# 14_-_RTC_EEPROM_GPIO_TOUCH_SCREEN.net
KiCad netlist of a schematic drawn in Altium Designer
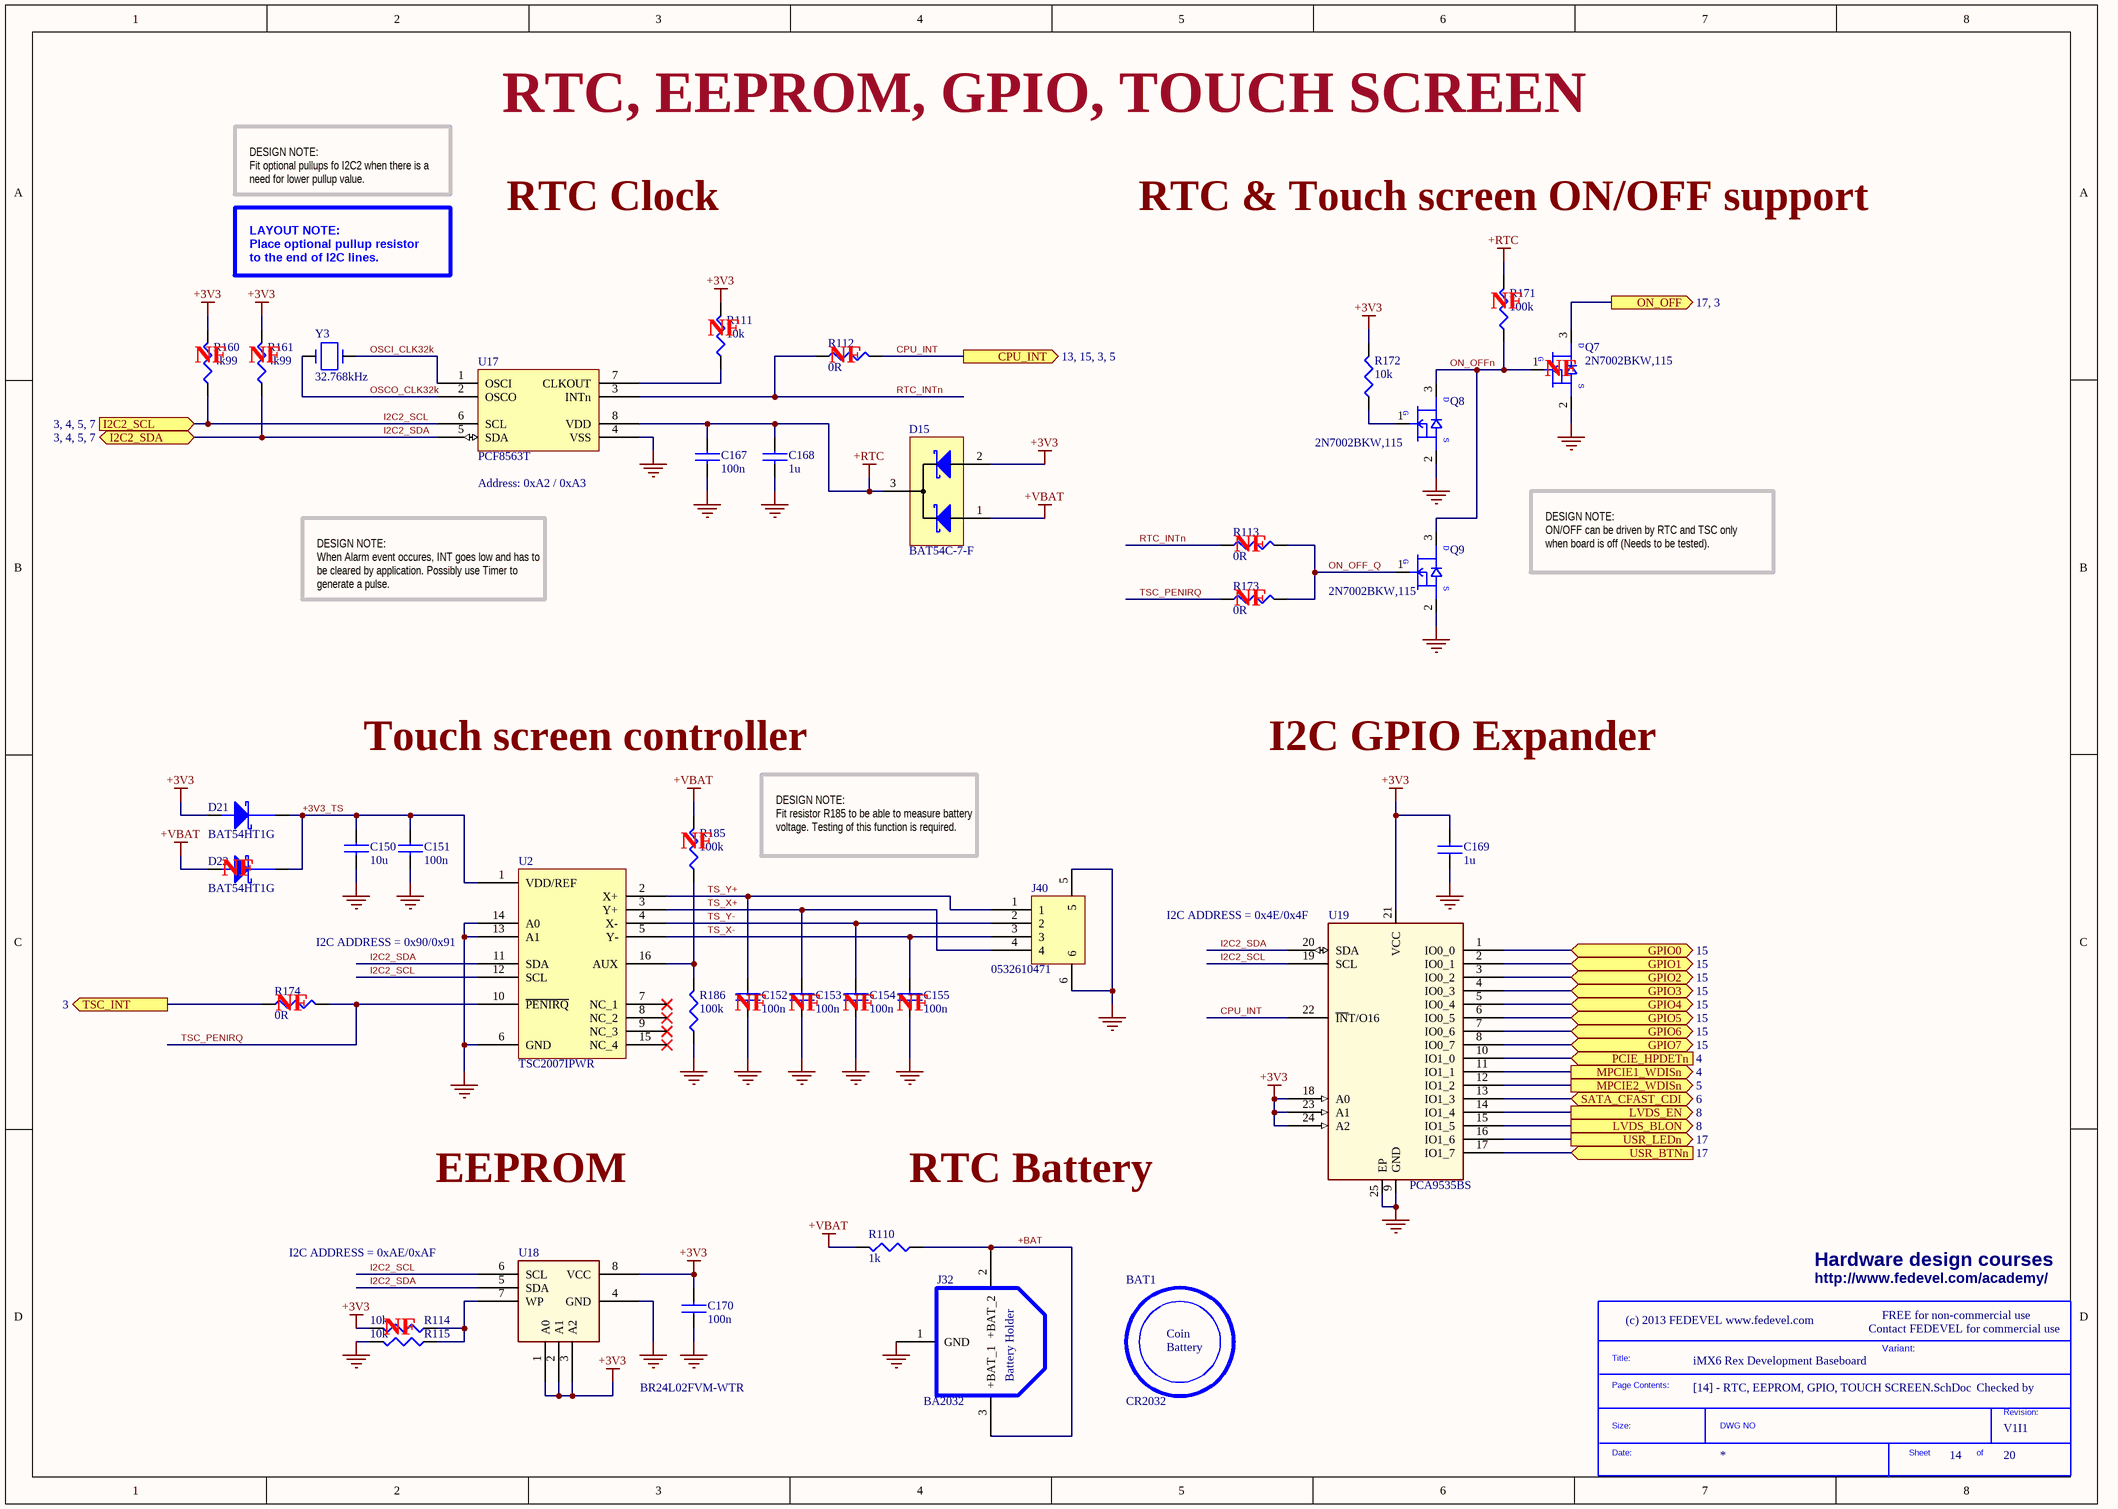
[diagram p0: [14] - RTC, EEPROM, GPIO, TOUCH SCREEN.SchDoc]

(export (version "E")
  (design (tool "Eeschema 10.0.6"))
  (components
    (comp (ref "BAT1")
      (value "CR2032")
      (description "BATTERY LITHIUM COIN 3V 20MM")
      (fields
        (field (name "MANUFACTURER") "Panasonic - BSG")
        (field (name ".CHECKED SCH") "RF")
        (field (name ".CHECKED PCB") "RF")
      )
      (libsource (lib "Integrated_Library_RF_FEB_2012") (part "CR2032"))
    )
    (comp (ref "C150")
      (value "10u")
      (footprint "C0603")
      (description "CAP CER 10UF 6.3V X5R 20% 0603")
      (fields
        (field (name "MANUFACTURER") "TDK Corporation")
        (field (name "MANUFACTURER PART NUMBER") "C1608X5R0J106M")
      )
      (libsource (lib "Integrated_Library_RF_FEB_2012") (part "C1608X5R0J106M"))
    )
    (comp (ref "C151")
      (value "100n")
      (footprint "C0402")
      (description "CAP CER .10UF 50V X5R 10% 0402")
      (fields
        (field (name "MANUFACTURER") "TDK Corporation")
        (field (name "MANUFACTURER PART NUMBER") "C1005X5R1H104K")
      )
      (libsource (lib "Integrated_Library_RF_FEB_2012") (part "C1005X5R1H104K"))
    )
    (comp (ref "C152")
      (value "100n")
      (footprint "C0402")
      (description "CAP CER .10UF 50V X5R 10% 0402")
      (fields
        (field (name "MANUFACTURER") "TDK Corporation")
        (field (name "MANUFACTURER PART NUMBER") "C1005X5R1H104K")
      )
      (libsource (lib "Integrated_Library_RF_FEB_2012") (part "C1005X5R1H104K"))
    )
    (comp (ref "C153")
      (value "100n")
      (footprint "C0402")
      (description "CAP CER .10UF 50V X5R 10% 0402")
      (fields
        (field (name "MANUFACTURER") "TDK Corporation")
        (field (name "MANUFACTURER PART NUMBER") "C1005X5R1H104K")
      )
      (libsource (lib "Integrated_Library_RF_FEB_2012") (part "C1005X5R1H104K"))
    )
    (comp (ref "C154")
      (value "100n")
      (footprint "C0402")
      (description "CAP CER .10UF 50V X5R 10% 0402")
      (fields
        (field (name "MANUFACTURER") "TDK Corporation")
        (field (name "MANUFACTURER PART NUMBER") "C1005X5R1H104K")
      )
      (libsource (lib "Integrated_Library_RF_FEB_2012") (part "C1005X5R1H104K"))
    )
    (comp (ref "C155")
      (value "100n")
      (footprint "C0402")
      (description "CAP CER .10UF 50V X5R 10% 0402")
      (fields
        (field (name "MANUFACTURER") "TDK Corporation")
        (field (name "MANUFACTURER PART NUMBER") "C1005X5R1H104K")
      )
      (libsource (lib "Integrated_Library_RF_FEB_2012") (part "C1005X5R1H104K"))
    )
    (comp (ref "C167")
      (value "100n")
      (footprint "C0402")
      (description "CAP CER .10UF 50V X5R 10% 0402")
      (fields
        (field (name "MANUFACTURER") "TDK Corporation")
        (field (name "MANUFACTURER PART NUMBER") "C1005X5R1H104K")
      )
      (libsource (lib "Integrated_Library_RF_FEB_2012") (part "C1005X5R1H104K"))
    )
    (comp (ref "C168")
      (value "1u")
      (footprint "C0402")
      (description "CAP CER 1.0UF 16V X5R 0402")
      (fields
        (field (name "MANUFACTURER") "TDK Corporation")
        (field (name "MANUFACTURER PART NUMBER") "C1005X5R1C105K")
      )
      (libsource (lib "Integrated_Library_RF_FEB_2012") (part "C1005X5R1C105K"))
    )
    (comp (ref "C169")
      (value "1u")
      (footprint "C0402")
      (description "CAP CER 1.0UF 16V X5R 0402")
      (fields
        (field (name "MANUFACTURER") "TDK Corporation")
        (field (name "MANUFACTURER PART NUMBER") "C1005X5R1C105K")
      )
      (libsource (lib "Integrated_Library_RF_FEB_2012") (part "C1005X5R1C105K"))
    )
    (comp (ref "C170")
      (value "100n")
      (footprint "C0402")
      (description "CAP CER .10UF 50V X5R 10% 0402")
      (fields
        (field (name "MANUFACTURER") "TDK Corporation")
        (field (name "MANUFACTURER PART NUMBER") "C1005X5R1H104K")
      )
      (libsource (lib "Integrated_Library_RF_FEB_2012") (part "C1005X5R1H104K"))
    )
    (comp (ref "D15")
      (value "BAT54C-7-F")
      (footprint "SOT-23-3-123")
      (description "DIODE SCHOTTKY DUAL 30V SOT23-3")
      (fields (field (name "MANUFACTURER") "Diodes Inc"))
      (libsource (lib "Integrated_Library_RF_FEB_2012") (part "BAT54C-7-F"))
    )
    (comp (ref "D21")
      (value "BAT54HT1G")
      (footprint "SOD323")
      (description "DIODE SCHOTTKY 30V 0.2A SOD323")
      (fields
        (field (name "MANUFACTURER") "Fairchild Semiconductor")
        (field (name ".CREATOR") "MM")
        (field (name ".CHECKED PCB") "RF, used by MM")
        (field (name ".CHECKED SCH") "MM")
      )
      (libsource (lib "Integrated_Library_RF_FEB_2012") (part "BAT54HT1G"))
    )
    (comp (ref "D22")
      (value "BAT54HT1G")
      (footprint "SOD323")
      (description "DIODE SCHOTTKY 30V 0.2A SOD323")
      (fields
        (field (name "MANUFACTURER") "Fairchild Semiconductor")
        (field (name ".CREATOR") "MM")
        (field (name ".CHECKED PCB") "RF, used by MM")
        (field (name ".CHECKED SCH") "MM")
      )
      (libsource (lib "Integrated_Library_RF_FEB_2012") (part "BAT54HT1G"))
    )
    (comp (ref "J32")
      (value "BA2032")
      (footprint "BA2032")
      (description "HOLDER COIN CELL CR2032 EJECT")
      (fields
        (field (name "MANUFACTURER") "MPD (Memory Protection Devices)")
        (field (name ".CREATOR") "MM")
        (field (name ".CHECKED PCB") "MM")
        (field (name ".CHECKED SCH") "RF, used by MM")
      )
      (libsource (lib "Integrated_Library_RF_FEB_2012") (part "BA2032"))
    )
    (comp (ref "J40")
      (value "0532610471")
      (footprint "0532610471")
      (description "CONN HEADER 4POS 1.25MM R/A SMD")
      (fields
        (field (name "MANUFACTURER") "Molex Inc")
        (field (name ".CREATOR") "MM")
        (field (name ".CHECKED PCB") "MM")
        (field (name ".CHECKED SCH") "MM")
      )
      (libsource (lib "Integrated_Library_RF_FEB_2012") (part "0532610471"))
    )
    (comp (ref "Q7")
      (value "2N7002BKW,115")
      (footprint "SC70_SOT323")
      (description "MOSFET N-CH 60V 310MA SOT323")
      (fields
        (field (name "MANUFACTURER") "NXP Semiconductors")
        (field (name ".CHECKED PCB") "RF")
        (field (name ".CHECKED SCH") "RF")
      )
      (libsource (lib "Integrated_Library_RF_FEB_2012") (part "2N7002BKW,115"))
    )
    (comp (ref "Q8")
      (value "2N7002BKW,115")
      (footprint "SC70_SOT323")
      (description "MOSFET N-CH 60V 310MA SOT323")
      (fields
        (field (name "MANUFACTURER") "NXP Semiconductors")
        (field (name ".CHECKED PCB") "RF")
        (field (name ".CHECKED SCH") "RF")
      )
      (libsource (lib "Integrated_Library_RF_FEB_2012") (part "2N7002BKW,115"))
    )
    (comp (ref "Q9")
      (value "2N7002BKW,115")
      (footprint "SC70_SOT323")
      (description "MOSFET N-CH 60V 310MA SOT323")
      (fields
        (field (name "MANUFACTURER") "NXP Semiconductors")
        (field (name ".CHECKED PCB") "RF")
        (field (name ".CHECKED SCH") "RF")
      )
      (libsource (lib "Integrated_Library_RF_FEB_2012") (part "2N7002BKW,115"))
    )
    (comp (ref "R110")
      (value "1k")
      (footprint "R0402")
      (description "RES 1.00K OHM 1/16W 1% 0402 SMD")
      (fields
        (field (name "MANUFACTURER") "Yageo")
        (field (name "MANUFACTURER PART NUMBER") "RC0402FR-071KL")
      )
      (libsource (lib "Integrated_Library_RF_FEB_2012") (part "RC0402FR-071KL"))
    )
    (comp (ref "R111")
      (value "10k")
      (footprint "R0402")
      (description "RES 10.0K OHM 1/16W 1% 0402 SMD")
      (fields
        (field (name "MANUFACTURER") "Yageo")
        (field (name "MANUFACTURER PART NUMBER") "RC0402FR-0710KL")
      )
      (libsource (lib "Integrated_Library_RF_FEB_2012") (part "RC0402FR-0710KL"))
    )
    (comp (ref "R112")
      (value "0R")
      (footprint "R0402")
      (description "RES 0.0 OHM 1/16W 0402 SMD")
      (fields
        (field (name "MANUFACTURER") "Yageo")
        (field (name "MANUFACTURER PART NUMBER") "RC0402JR-070RL")
      )
      (libsource (lib "Integrated_Library_RF_FEB_2012") (part "RC0402JR-070RL"))
    )
    (comp (ref "R113")
      (value "0R")
      (footprint "R0402")
      (description "RES 0.0 OHM 1/16W 0402 SMD")
      (fields
        (field (name "MANUFACTURER") "Yageo")
        (field (name "MANUFACTURER PART NUMBER") "RC0402JR-070RL")
      )
      (libsource (lib "Integrated_Library_RF_FEB_2012") (part "RC0402JR-070RL"))
    )
    (comp (ref "R114")
      (value "10k")
      (footprint "R0402")
      (description "RES 10.0K OHM 1/16W 1% 0402 SMD")
      (fields
        (field (name "MANUFACTURER") "Yageo")
        (field (name "MANUFACTURER PART NUMBER") "RC0402FR-0710KL")
      )
      (libsource (lib "Integrated_Library_RF_FEB_2012") (part "RC0402FR-0710KL"))
    )
    (comp (ref "R115")
      (value "10k")
      (footprint "R0402")
      (description "RES 10.0K OHM 1/16W 1% 0402 SMD")
      (fields
        (field (name "MANUFACTURER") "Yageo")
        (field (name "MANUFACTURER PART NUMBER") "RC0402FR-0710KL")
      )
      (libsource (lib "Integrated_Library_RF_FEB_2012") (part "RC0402FR-0710KL"))
    )
    (comp (ref "R160")
      (value "4k99")
      (footprint "R0402")
      (description "RES TF 4.99K OHM 1% 1/16W 0402")
      (fields
        (field (name "MANUFACTURER") "Stackpole Electronics Inc")
        (field (name "MANUFACTURER PART NUMBER") "RMCF0402FT4K99")
      )
      (libsource (lib "Integrated_Library_RF_FEB_2012") (part "RMCF0402FT4K99"))
    )
    (comp (ref "R161")
      (value "4k99")
      (footprint "R0402")
      (description "RES TF 4.99K OHM 1% 1/16W 0402")
      (fields
        (field (name "MANUFACTURER") "Stackpole Electronics Inc")
        (field (name "MANUFACTURER PART NUMBER") "RMCF0402FT4K99")
      )
      (libsource (lib "Integrated_Library_RF_FEB_2012") (part "RMCF0402FT4K99"))
    )
    (comp (ref "R171")
      (value "100k")
      (footprint "R0402")
      (description "RES 100K OHM 1/16W 1% 0402 SMD")
      (fields
        (field (name "MANUFACTURER") "Stackpole Electronics Inc")
        (field (name "MANUFACTURER PART NUMBER") "RMCF0402FT100K")
      )
      (libsource (lib "Integrated_Library_RF_FEB_2012") (part "RMCF0402FT100K"))
    )
    (comp (ref "R172")
      (value "10k")
      (footprint "R0402")
      (description "RES 10.0K OHM 1/16W 1% 0402 SMD")
      (fields
        (field (name "MANUFACTURER") "Yageo")
        (field (name "MANUFACTURER PART NUMBER") "RC0402FR-0710KL")
      )
      (libsource (lib "Integrated_Library_RF_FEB_2012") (part "RC0402FR-0710KL"))
    )
    (comp (ref "R173")
      (value "0R")
      (footprint "R0402")
      (description "RES 0.0 OHM 1/16W 0402 SMD")
      (fields
        (field (name "MANUFACTURER") "Yageo")
        (field (name "MANUFACTURER PART NUMBER") "RC0402JR-070RL")
      )
      (libsource (lib "Integrated_Library_RF_FEB_2012") (part "RC0402JR-070RL"))
    )
    (comp (ref "R174")
      (value "0R")
      (footprint "R0402")
      (description "RES 0.0 OHM 1/16W 0402 SMD")
      (fields
        (field (name "MANUFACTURER") "Yageo")
        (field (name "MANUFACTURER PART NUMBER") "RC0402JR-070RL")
      )
      (libsource (lib "Integrated_Library_RF_FEB_2012") (part "RC0402JR-070RL"))
    )
    (comp (ref "R185")
      (value "100k")
      (footprint "R0402")
      (description "RES 100K OHM 1/16W 1% 0402 SMD")
      (fields
        (field (name "MANUFACTURER") "Stackpole Electronics Inc")
        (field (name "MANUFACTURER PART NUMBER") "RMCF0402FT100K")
      )
      (libsource (lib "Integrated_Library_RF_FEB_2012") (part "RMCF0402FT100K"))
    )
    (comp (ref "R186")
      (value "100k")
      (footprint "R0402")
      (description "RES 100K OHM 1/16W 1% 0402 SMD")
      (fields
        (field (name "MANUFACTURER") "Stackpole Electronics Inc")
        (field (name "MANUFACTURER PART NUMBER") "RMCF0402FT100K")
      )
      (libsource (lib "Integrated_Library_RF_FEB_2012") (part "RMCF0402FT100K"))
    )
    (comp (ref "U2")
      (value "TSC2007IPWR")
      (footprint "PW (R-PDGO-G16)")
      (description "IC TOUCH SCREEN 12BIT 16TSSOP")
      (fields
        (field (name "MANUFACTURER") "Texas Instruments")
        (field (name ".CREATOR") "MM")
        (field (name ".CHECKED PCB") "MM")
        (field (name ".CHECKED SCH") "MM")
      )
      (libsource (lib "Integrated_Library_RF_FEB_2012") (part "TSC2007IPWR"))
    )
    (comp (ref "U17")
      (value "PCF8563T")
      (footprint "8_SOIC_3.9MM")
      (description "IC REAL TIME CLK/CALENDAR 8-SOIC")
      (fields
        (field (name "MANUFACTURER") "NXP Semiconductors")
        (field (name "MANUFACTURER PART NUMBER") "PCF8563T/F4,118")
      )
      (libsource (lib "Integrated_Library_RF_FEB_2012") (part "PCF8563T"))
    )
    (comp (ref "U18")
      (value "BR24L02FVM-WTR")
      (footprint "MSOP8 _SMALLER")
      (description "IC EEPROM 2KBIT 400KHZ 8MSOP")
      (fields
        (field (name "MANUFACTURER") "Rohm Semiconductor")
        (field (name ".CHECKED PCB") "RF")
        (field (name ".CHECKED SCH") "RF")
      )
      (libsource (lib "Integrated_Library_RF_FEB_2012") (part "BR24L02FVM-WTR"))
    )
    (comp (ref "U19")
      (value "PCA9535BS")
      (footprint "HVQFN24_4x4MM")
      (description "IC I/O EXPANDER I2C 16B 24HVQFN")
      (fields
        (field (name "MANUFACTURER") "NXP Semiconductors")
        (field (name "MANUFACTURER PART NUMBER") "PCA9535BS,118")
        (field (name ".CHECKED PCB") "RF")
        (field (name ".CHECKED SCH") "RF")
      )
      (libsource (lib "Integrated_Library_RF_FEB_2012") (part "PCA9535BS,118"))
    )
    (comp (ref "Y3")
      (value "32.768kHz")
      (footprint "ABS06")
      (description "CRYSTAL 32.768 KHZ 9.0 PF SMD")
      (fields
        (field (name "MANUFACTURER") "Abracon Corporation")
        (field (name "MANUFACTURER PART NUMBER") "ABS06-32.768KHZ-9-1-T")
      )
      (libsource (lib "Integrated_Library_RF_FEB_2012") (part "ABS06-32.768KHZ-9-1-T"))
    )
  )
  (nets
    (net (code "1") (name "+3V3") (class "Default")
      (node (ref "C169") (pin "2") (pinfunction "2_2") (pintype "passive"))
      (node (ref "C170") (pin "2") (pinfunction "2_2") (pintype "passive"))
      (node (ref "D15") (pin "2") (pinfunction "2_2") (pintype "passive"))
      (node (ref "D21") (pin "2") (pinfunction "Anode_2") (pintype "passive"))
      (node (ref "R111") (pin "2") (pinfunction "2_2") (pintype "passive"))
      (node (ref "R114") (pin "2") (pinfunction "2_2") (pintype "passive"))
      (node (ref "R160") (pin "2") (pinfunction "2_2") (pintype "passive"))
      (node (ref "R161") (pin "2") (pinfunction "2_2") (pintype "passive"))
      (node (ref "R172") (pin "2") (pinfunction "2_2") (pintype "passive"))
      (node (ref "U18") (pin "1") (pinfunction "A0_1") (pintype "passive"))
      (node (ref "U18") (pin "2") (pinfunction "A1_2") (pintype "passive"))
      (node (ref "U18") (pin "3") (pinfunction "A2_3") (pintype "passive"))
      (node (ref "U18") (pin "8") (pinfunction "VCC_8") (pintype "power_in"))
      (node (ref "U19") (pin "18") (pinfunction "A0_18") (pintype "input"))
      (node (ref "U19") (pin "21") (pinfunction "VCC_21") (pintype "power_in"))
      (node (ref "U19") (pin "23") (pinfunction "A1_23") (pintype "input"))
      (node (ref "U19") (pin "24") (pinfunction "A2_24") (pintype "input"))
    )
    (net (code "2") (name "+RTC") (class "Default")
      (node (ref "C167") (pin "1") (pinfunction "1_1") (pintype "passive"))
      (node (ref "C168") (pin "1") (pinfunction "1_1") (pintype "passive"))
      (node (ref "D15") (pin "3") (pinfunction "3_3") (pintype "passive"))
      (node (ref "R171") (pin "2") (pinfunction "2_2") (pintype "passive"))
      (node (ref "U17") (pin "8") (pinfunction "VDD_8") (pintype "power_in"))
    )
    (net (code "3") (name "+VBAT") (class "Default")
      (node (ref "D15") (pin "1") (pinfunction "1_1") (pintype "passive"))
      (node (ref "D22") (pin "2") (pinfunction "Anode_2") (pintype "passive"))
      (node (ref "R110") (pin "2") (pinfunction "2_2") (pintype "passive"))
      (node (ref "R185") (pin "2") (pinfunction "2_2") (pintype "passive"))
    )
    (net (code "4") (name "/+3V3_TS") (class "Default")
      (node (ref "C150") (pin "1") (pinfunction "1_1") (pintype "passive"))
      (node (ref "C151") (pin "1") (pinfunction "1_1") (pintype "passive"))
      (node (ref "D21") (pin "1") (pinfunction "Cathode_1") (pintype "passive"))
      (node (ref "D22") (pin "1") (pinfunction "Cathode_1") (pintype "passive"))
      (node (ref "U2") (pin "1") (pinfunction "VDD/REF_1") (pintype "passive"))
    )
    (net (code "5") (name "/+BAT") (class "Default")
      (node (ref "J32") (pin "2") (pinfunction "+BAT_2_2") (pintype "passive"))
      (node (ref "J32") (pin "3") (pinfunction "+BAT_1_3") (pintype "passive"))
      (node (ref "R110") (pin "1") (pinfunction "1_1") (pintype "passive"))
    )
    (net (code "6") (name "/CPU_INT") (class "Default")
      (node (ref "R112") (pin "2") (pinfunction "2_2") (pintype "passive"))
      (node (ref "U19") (pin "22") (pinfunction "~{IN}T/O16_22") (pintype "passive"))
    )
    (net (code "7") (name "/GPIO0") (class "Default")
      (node (ref "U19") (pin "1") (pinfunction "IO0_0_1") (pintype "passive"))
    )
    (net (code "8") (name "/GPIO1") (class "Default")
      (node (ref "U19") (pin "2") (pinfunction "IO0_1_2") (pintype "passive"))
    )
    (net (code "9") (name "/GPIO2") (class "Default")
      (node (ref "U19") (pin "3") (pinfunction "IO0_2_3") (pintype "passive"))
    )
    (net (code "10") (name "/GPIO3") (class "Default")
      (node (ref "U19") (pin "4") (pinfunction "IO0_3_4") (pintype "passive"))
    )
    (net (code "11") (name "/GPIO4") (class "Default")
      (node (ref "U19") (pin "5") (pinfunction "IO0_4_5") (pintype "passive"))
    )
    (net (code "12") (name "/GPIO5") (class "Default")
      (node (ref "U19") (pin "6") (pinfunction "IO0_5_6") (pintype "passive"))
    )
    (net (code "13") (name "/GPIO6") (class "Default")
      (node (ref "U19") (pin "7") (pinfunction "IO0_6_7") (pintype "passive"))
    )
    (net (code "14") (name "/GPIO7") (class "Default")
      (node (ref "U19") (pin "8") (pinfunction "IO0_7_8") (pintype "passive"))
    )
    (net (code "15") (name "/I2C2_SCL") (class "Default")
      (node (ref "R160") (pin "1") (pinfunction "1_1") (pintype "passive"))
      (node (ref "U17") (pin "6") (pinfunction "SCL_6") (pintype "passive"))
      (node (ref "U18") (pin "6") (pinfunction "SCL_6") (pintype "passive"))
      (node (ref "U19") (pin "19") (pinfunction "SCL_19") (pintype "passive"))
      (node (ref "U2") (pin "12") (pinfunction "SCL_12") (pintype "passive"))
    )
    (net (code "16") (name "/I2C2_SDA") (class "Default")
      (node (ref "R161") (pin "1") (pinfunction "1_1") (pintype "passive"))
      (node (ref "U17") (pin "5") (pinfunction "SDA_5") (pintype "bidirectional"))
      (node (ref "U18") (pin "5") (pinfunction "SDA_5") (pintype "passive"))
      (node (ref "U19") (pin "20") (pinfunction "SDA_20") (pintype "bidirectional"))
      (node (ref "U2") (pin "11") (pinfunction "SDA_11") (pintype "passive"))
    )
    (net (code "17") (name "/LVDS_BLON") (class "Default")
      (node (ref "U19") (pin "15") (pinfunction "IO1_5_15") (pintype "passive"))
    )
    (net (code "18") (name "/LVDS_EN") (class "Default")
      (node (ref "U19") (pin "14") (pinfunction "IO1_4_14") (pintype "passive"))
    )
    (net (code "19") (name "/MPCIE1_WDISn") (class "Default")
      (node (ref "U19") (pin "11") (pinfunction "IO1_1_11") (pintype "passive"))
    )
    (net (code "20") (name "/MPCIE2_WDISn") (class "Default")
      (node (ref "U19") (pin "12") (pinfunction "IO1_2_12") (pintype "passive"))
    )
    (net (code "21") (name "/ON_OFF") (class "Default")
      (node (ref "Q7") (pin "3") (pinfunction "DRAIN_3") (pintype "passive"))
    )
    (net (code "22") (name "/ON_OFF_Q") (class "Default")
      (node (ref "Q9") (pin "1") (pinfunction "GATE_1") (pintype "passive"))
      (node (ref "R113") (pin "2") (pinfunction "2_2") (pintype "passive"))
      (node (ref "R173") (pin "2") (pinfunction "2_2") (pintype "passive"))
    )
    (net (code "23") (name "/ON_OFFn") (class "Default")
      (node (ref "Q7") (pin "1") (pinfunction "GATE_1") (pintype "passive"))
      (node (ref "Q8") (pin "3") (pinfunction "DRAIN_3") (pintype "passive"))
      (node (ref "Q9") (pin "3") (pinfunction "DRAIN_3") (pintype "passive"))
      (node (ref "R171") (pin "1") (pinfunction "1_1") (pintype "passive"))
    )
    (net (code "24") (name "/OSCI_CLK32k") (class "Default")
      (node (ref "U17") (pin "1") (pinfunction "OSCI_1") (pintype "passive"))
      (node (ref "Y3") (pin "1") (pinfunction "1_1") (pintype "passive"))
    )
    (net (code "25") (name "/OSCO_CLK32k") (class "Default")
      (node (ref "U17") (pin "2") (pinfunction "OSCO_2") (pintype "passive"))
      (node (ref "Y3") (pin "2") (pinfunction "2_2") (pintype "passive"))
    )
    (net (code "26") (name "/PCIE_HPDETn") (class "Default")
      (node (ref "U19") (pin "10") (pinfunction "IO1_0_10") (pintype "passive"))
    )
    (net (code "27") (name "/RTC_INTn") (class "Default")
      (node (ref "R112") (pin "1") (pinfunction "1_1") (pintype "passive"))
      (node (ref "R113") (pin "1") (pinfunction "1_1") (pintype "passive"))
      (node (ref "U17") (pin "3") (pinfunction "INTn_3") (pintype "open_collector"))
    )
    (net (code "28") (name "/SATA_CFAST_CDI") (class "Default")
      (node (ref "U19") (pin "13") (pinfunction "IO1_3_13") (pintype "passive"))
    )
    (net (code "29") (name "/TSC_INT") (class "Default")
      (node (ref "R174") (pin "1") (pinfunction "1_1") (pintype "passive"))
    )
    (net (code "30") (name "/TSC_PENIRQ") (class "Default")
      (node (ref "R173") (pin "1") (pinfunction "1_1") (pintype "passive"))
      (node (ref "R174") (pin "2") (pinfunction "2_2") (pintype "passive"))
      (node (ref "U2") (pin "10") (pinfunction "~{PENIRQ}_10") (pintype "passive"))
    )
    (net (code "31") (name "/TS_X+") (class "Default")
      (node (ref "C153") (pin "1") (pinfunction "1_1") (pintype "passive"))
      (node (ref "J40") (pin "4") (pinfunction "4_4") (pintype "passive"))
      (node (ref "U2") (pin "3") (pinfunction "Y+_3") (pintype "passive"))
    )
    (net (code "32") (name "/TS_X-") (class "Default")
      (node (ref "C155") (pin "1") (pinfunction "1_1") (pintype "passive"))
      (node (ref "J40") (pin "3") (pinfunction "3_3") (pintype "passive"))
      (node (ref "U2") (pin "5") (pinfunction "Y-_5") (pintype "passive"))
    )
    (net (code "33") (name "/TS_Y+") (class "Default")
      (node (ref "C152") (pin "1") (pinfunction "1_1") (pintype "passive"))
      (node (ref "J40") (pin "1") (pinfunction "1_1") (pintype "passive"))
      (node (ref "U2") (pin "2") (pinfunction "X+_2") (pintype "passive"))
    )
    (net (code "34") (name "/TS_Y-") (class "Default")
      (node (ref "C154") (pin "1") (pinfunction "1_1") (pintype "passive"))
      (node (ref "J40") (pin "2") (pinfunction "2_2") (pintype "passive"))
      (node (ref "U2") (pin "4") (pinfunction "X-_4") (pintype "passive"))
    )
    (net (code "35") (name "/USR_BTNn") (class "Default")
      (node (ref "U19") (pin "17") (pinfunction "IO1_7_17") (pintype "passive"))
    )
    (net (code "36") (name "/USR_LEDn") (class "Default")
      (node (ref "U19") (pin "16") (pinfunction "IO1_6_16") (pintype "passive"))
    )
    (net (code "37") (name "GND") (class "Default")
      (node (ref "C150") (pin "2") (pinfunction "2_2") (pintype "passive"))
      (node (ref "C151") (pin "2") (pinfunction "2_2") (pintype "passive"))
      (node (ref "C152") (pin "2") (pinfunction "2_2") (pintype "passive"))
      (node (ref "C153") (pin "2") (pinfunction "2_2") (pintype "passive"))
      (node (ref "C154") (pin "2") (pinfunction "2_2") (pintype "passive"))
      (node (ref "C155") (pin "2") (pinfunction "2_2") (pintype "passive"))
      (node (ref "C167") (pin "2") (pinfunction "2_2") (pintype "passive"))
      (node (ref "C168") (pin "2") (pinfunction "2_2") (pintype "passive"))
      (node (ref "C169") (pin "1") (pinfunction "1_1") (pintype "passive"))
      (node (ref "C170") (pin "1") (pinfunction "1_1") (pintype "passive"))
      (node (ref "J32") (pin "1") (pinfunction "GND_1") (pintype "passive"))
      (node (ref "J40") (pin "5") (pinfunction "5_5") (pintype "passive"))
      (node (ref "J40") (pin "6") (pinfunction "6_6") (pintype "passive"))
      (node (ref "Q7") (pin "2") (pinfunction "SOURCE_2") (pintype "passive"))
      (node (ref "Q8") (pin "2") (pinfunction "SOURCE_2") (pintype "passive"))
      (node (ref "Q9") (pin "2") (pinfunction "SOURCE_2") (pintype "passive"))
      (node (ref "R115") (pin "2") (pinfunction "2_2") (pintype "passive"))
      (node (ref "R186") (pin "1") (pinfunction "1_1") (pintype "passive"))
      (node (ref "U17") (pin "4") (pinfunction "VSS_4") (pintype "power_in"))
      (node (ref "U18") (pin "4") (pinfunction "GND_4") (pintype "power_in"))
      (node (ref "U19") (pin "25") (pinfunction "EP_25") (pintype "power_in"))
      (node (ref "U19") (pin "9") (pinfunction "GND_9") (pintype "power_in"))
      (node (ref "U2") (pin "13") (pinfunction "A1_13") (pintype "passive"))
      (node (ref "U2") (pin "14") (pinfunction "A0_14") (pintype "passive"))
      (node (ref "U2") (pin "6") (pinfunction "GND_6") (pintype "passive"))
    )
    (net (code "38") (name "Net-(Q8-GATE)") (class "Default")
      (node (ref "Q8") (pin "1") (pinfunction "GATE_1") (pintype "passive"))
      (node (ref "R172") (pin "1") (pinfunction "1_1") (pintype "passive"))
    )
    (net (code "39") (name "Net-(U2-AUX)") (class "Default")
      (node (ref "R185") (pin "1") (pinfunction "1_1") (pintype "passive"))
      (node (ref "R186") (pin "2") (pinfunction "2_2") (pintype "passive"))
      (node (ref "U2") (pin "16") (pinfunction "AUX_16") (pintype "passive"))
    )
    (net (code "40") (name "Net-(U17-CLKOUT)") (class "Default")
      (node (ref "R111") (pin "1") (pinfunction "1_1") (pintype "passive"))
      (node (ref "U17") (pin "7") (pinfunction "CLKOUT_7") (pintype "open_collector"))
    )
    (net (code "41") (name "Net-(U18-WP)") (class "Default")
      (node (ref "R114") (pin "1") (pinfunction "1_1") (pintype "passive"))
      (node (ref "R115") (pin "1") (pinfunction "1_1") (pintype "passive"))
      (node (ref "U18") (pin "7") (pinfunction "WP_7") (pintype "passive"))
    )
    (net (code "42") (name "unconnected-(U2-NC_1-Pad7)") (class "Default")
      (node (ref "U2") (pin "7") (pinfunction "NC_1_7") (pintype "passive+no_connect"))
    )
    (net (code "43") (name "unconnected-(U2-NC_2-Pad8)") (class "Default")
      (node (ref "U2") (pin "8") (pinfunction "NC_2_8") (pintype "passive+no_connect"))
    )
    (net (code "44") (name "unconnected-(U2-NC_3-Pad9)") (class "Default")
      (node (ref "U2") (pin "9") (pinfunction "NC_3_9") (pintype "passive+no_connect"))
    )
    (net (code "45") (name "unconnected-(U2-NC_4-Pad15)") (class "Default")
      (node (ref "U2") (pin "15") (pinfunction "NC_4_15") (pintype "passive+no_connect"))
    )
  )
)
